# Driver_Board_Invert.net
KiCad netlist of a schematic drawn in EAGLE
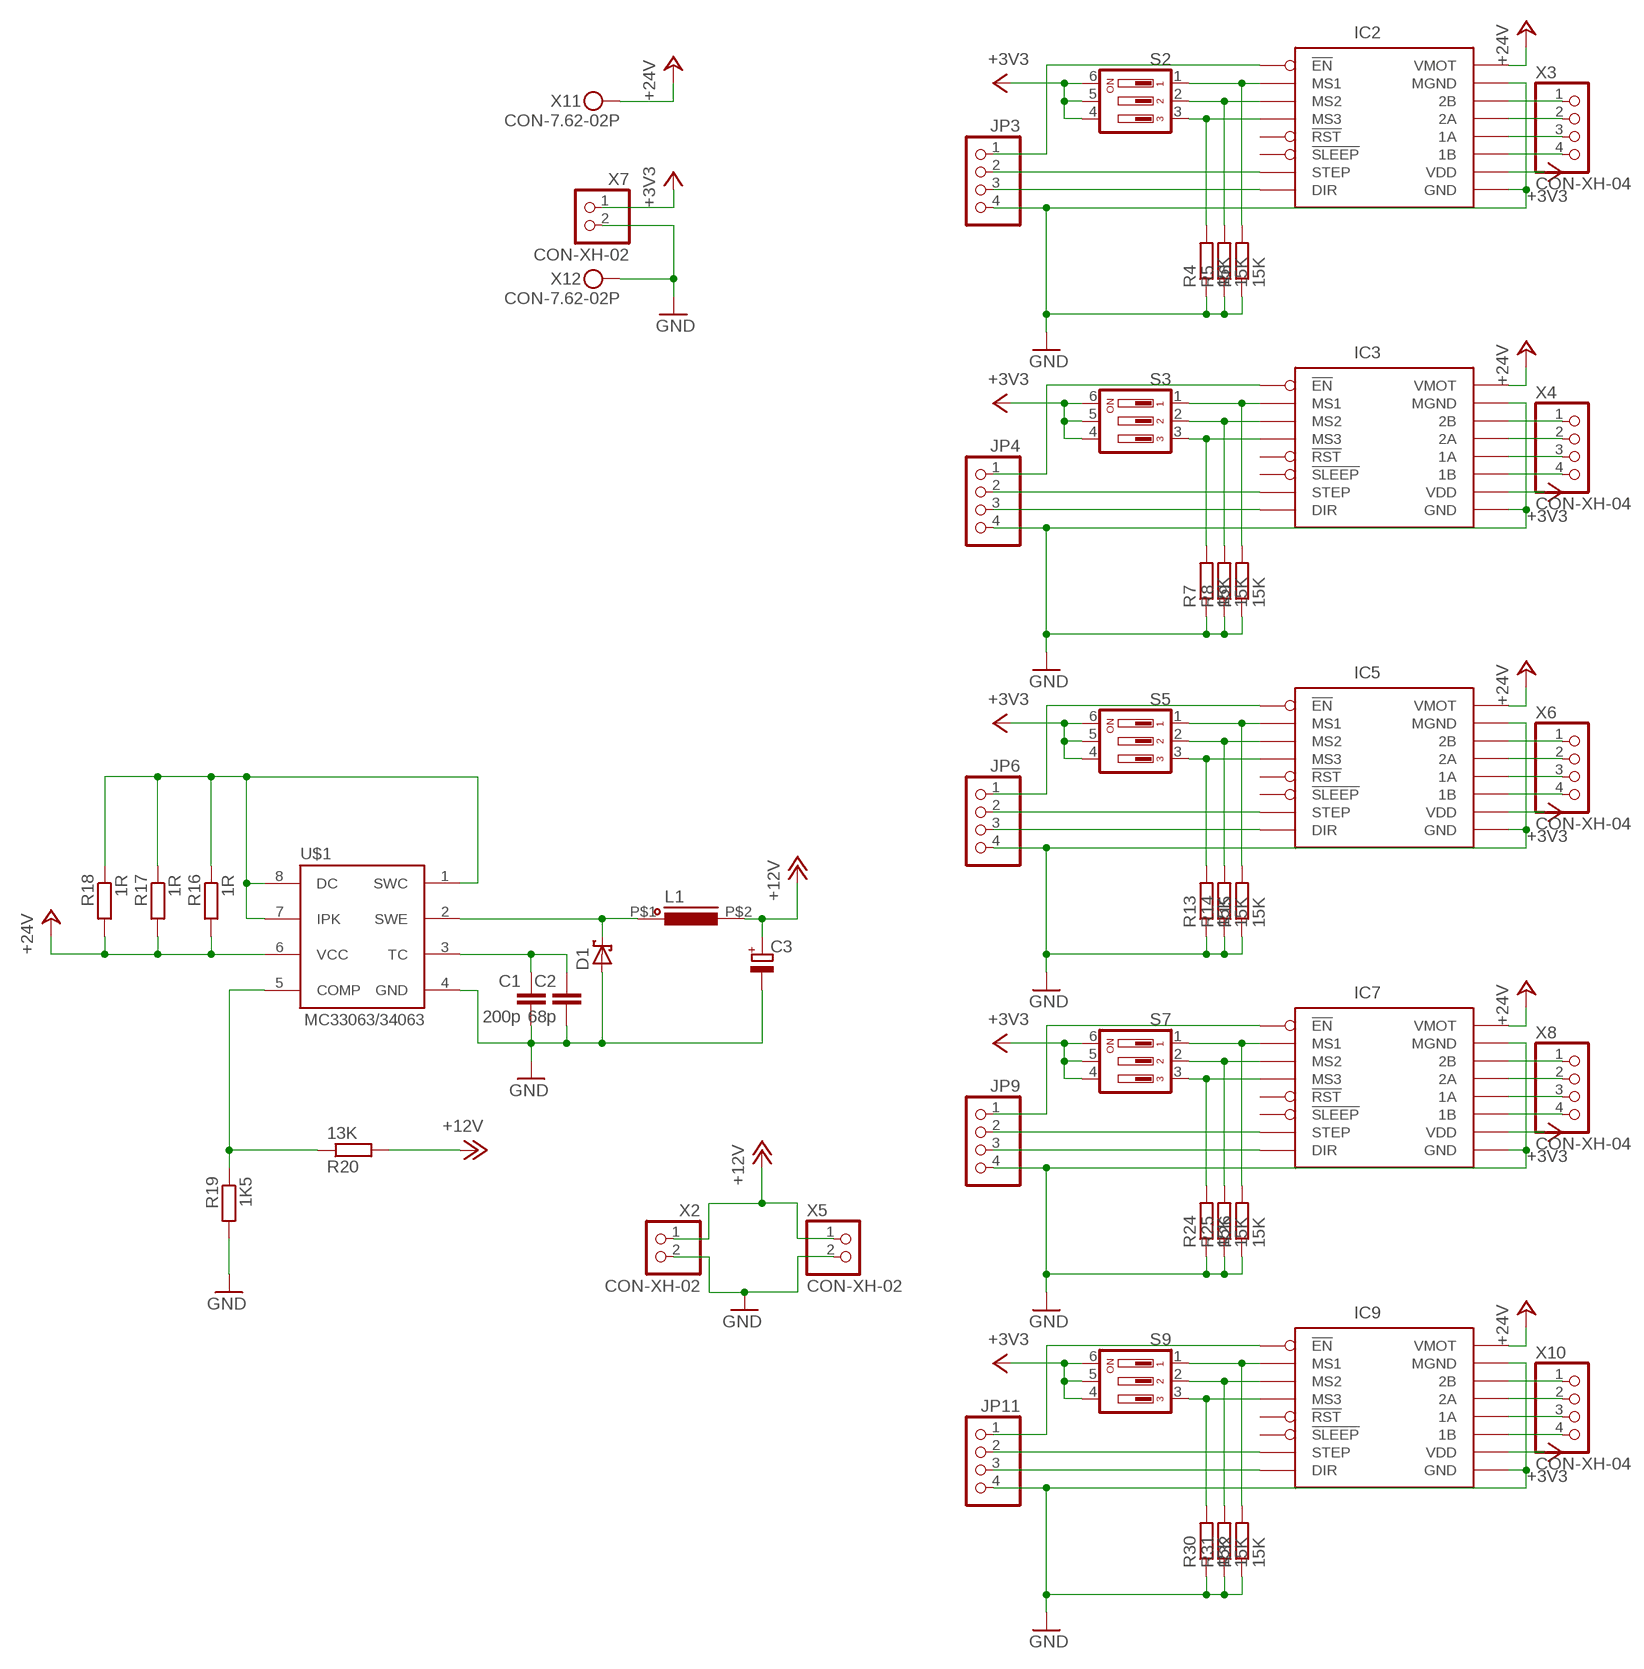
[diagram p0: schematic, sheet 1]

(export (version "E")
  (design (tool "Eeschema 10.0.6"))
  (components
    (comp (ref "C1")
      (value "200p")
      (footprint "eagle-import:C0805")
      (libsource (lib "eagle-import") (part "CAP_0805"))
    )
    (comp (ref "C2")
      (value "68p")
      (footprint "eagle-import:C0805")
      (libsource (lib "eagle-import") (part "CAP_0805"))
    )
    (comp (ref "C3")
      (value "CAP-POL_E3.5-8")
      (footprint "eagle-import:E3,5-8")
      (libsource (lib "eagle-import") (part "CAP-POL_E3.5-8"))
    )
    (comp (ref "D1")
      (value "DIODE-SH_SMA")
      (footprint "eagle-import:DO214AC")
      (libsource (lib "eagle-import") (part "DIODE-SH_SMA"))
    )
    (comp (ref "IC2")
      (value "STEP-DRVST820-REV")
      (footprint "eagle-import:DRV-ST820-REV")
      (libsource (lib "eagle-import") (part "STEP-DRVST820-REV"))
    )
    (comp (ref "IC3")
      (value "STEP-DRVST820-REV")
      (footprint "eagle-import:DRV-ST820-REV")
      (libsource (lib "eagle-import") (part "STEP-DRVST820-REV"))
    )
    (comp (ref "IC5")
      (value "STEP-DRVST820-REV")
      (footprint "eagle-import:DRV-ST820-REV")
      (libsource (lib "eagle-import") (part "STEP-DRVST820-REV"))
    )
    (comp (ref "IC7")
      (value "STEP-DRVST820-REV")
      (footprint "eagle-import:DRV-ST820-REV")
      (libsource (lib "eagle-import") (part "STEP-DRVST820-REV"))
    )
    (comp (ref "IC9")
      (value "STEP-DRVST820-REV")
      (footprint "eagle-import:DRV-ST820-REV")
      (libsource (lib "eagle-import") (part "STEP-DRVST820-REV"))
    )
    (comp (ref "JP3")
      (value "PINHD-1X4")
      (footprint "eagle-import:1X04")
      (libsource (lib "eagle-import") (part "PINHD-1X4"))
    )
    (comp (ref "JP4")
      (value "PINHD-1X4")
      (footprint "eagle-import:1X04")
      (libsource (lib "eagle-import") (part "PINHD-1X4"))
    )
    (comp (ref "JP6")
      (value "PINHD-1X4")
      (footprint "eagle-import:1X04")
      (libsource (lib "eagle-import") (part "PINHD-1X4"))
    )
    (comp (ref "JP9")
      (value "PINHD-1X4")
      (footprint "eagle-import:1X04")
      (libsource (lib "eagle-import") (part "PINHD-1X4"))
    )
    (comp (ref "JP11")
      (value "PINHD-1X4")
      (footprint "eagle-import:1X04")
      (libsource (lib "eagle-import") (part "PINHD-1X4"))
    )
    (comp (ref "L1")
      (value "INDUCTORCW68")
      (footprint "eagle-import:CW68")
      (libsource (lib "eagle-import") (part "INDUCTORCW68"))
    )
    (comp (ref "R4")
      (value "15K")
      (footprint "eagle-import:RESC2012X50")
      (libsource (lib "eagle-import") (part "R_R0805"))
    )
    (comp (ref "R5")
      (value "15K")
      (footprint "eagle-import:RESC2012X50")
      (libsource (lib "eagle-import") (part "R_R0805"))
    )
    (comp (ref "R6")
      (value "15K")
      (footprint "eagle-import:RESC2012X50")
      (libsource (lib "eagle-import") (part "R_R0805"))
    )
    (comp (ref "R7")
      (value "15K")
      (footprint "eagle-import:RESC2012X50")
      (libsource (lib "eagle-import") (part "R_R0805"))
    )
    (comp (ref "R8")
      (value "15K")
      (footprint "eagle-import:RESC2012X50")
      (libsource (lib "eagle-import") (part "R_R0805"))
    )
    (comp (ref "R9")
      (value "15K")
      (footprint "eagle-import:RESC2012X50")
      (libsource (lib "eagle-import") (part "R_R0805"))
    )
    (comp (ref "R13")
      (value "15K")
      (footprint "eagle-import:RESC2012X50")
      (libsource (lib "eagle-import") (part "R_R0805"))
    )
    (comp (ref "R14")
      (value "15K")
      (footprint "eagle-import:RESC2012X50")
      (libsource (lib "eagle-import") (part "R_R0805"))
    )
    (comp (ref "R15")
      (value "15K")
      (footprint "eagle-import:RESC2012X50")
      (libsource (lib "eagle-import") (part "R_R0805"))
    )
    (comp (ref "R16")
      (value "1R")
      (footprint "eagle-import:R0805")
      (libsource (lib "eagle-import") (part "R_0805"))
    )
    (comp (ref "R17")
      (value "1R")
      (footprint "eagle-import:R0805")
      (libsource (lib "eagle-import") (part "R_0805"))
    )
    (comp (ref "R18")
      (value "1R")
      (footprint "eagle-import:R0805")
      (libsource (lib "eagle-import") (part "R_0805"))
    )
    (comp (ref "R19")
      (value "1K5")
      (footprint "eagle-import:R0805")
      (libsource (lib "eagle-import") (part "R_0805"))
    )
    (comp (ref "R20")
      (value "13K")
      (footprint "eagle-import:R0805")
      (libsource (lib "eagle-import") (part "R_0805"))
    )
    (comp (ref "R24")
      (value "15K")
      (footprint "eagle-import:RESC2012X50")
      (libsource (lib "eagle-import") (part "R_R0805"))
    )
    (comp (ref "R25")
      (value "15K")
      (footprint "eagle-import:RESC2012X50")
      (libsource (lib "eagle-import") (part "R_R0805"))
    )
    (comp (ref "R26")
      (value "15K")
      (footprint "eagle-import:RESC2012X50")
      (libsource (lib "eagle-import") (part "R_R0805"))
    )
    (comp (ref "R30")
      (value "15K")
      (footprint "eagle-import:RESC2012X50")
      (libsource (lib "eagle-import") (part "R_R0805"))
    )
    (comp (ref "R31")
      (value "15K")
      (footprint "eagle-import:RESC2012X50")
      (libsource (lib "eagle-import") (part "R_R0805"))
    )
    (comp (ref "R32")
      (value "15K")
      (footprint "eagle-import:RESC2012X50")
      (libsource (lib "eagle-import") (part "R_R0805"))
    )
    (comp (ref "S2")
      (value "SW-DIP03S")
      (footprint "eagle-import:DIP03YL")
      (libsource (lib "eagle-import") (part "SW-DIP03S"))
    )
    (comp (ref "S3")
      (value "SW-DIP03S")
      (footprint "eagle-import:DIP03YL")
      (libsource (lib "eagle-import") (part "SW-DIP03S"))
    )
    (comp (ref "S5")
      (value "SW-DIP03S")
      (footprint "eagle-import:DIP03YL")
      (libsource (lib "eagle-import") (part "SW-DIP03S"))
    )
    (comp (ref "S7")
      (value "SW-DIP03S")
      (footprint "eagle-import:DIP03YL")
      (libsource (lib "eagle-import") (part "SW-DIP03S"))
    )
    (comp (ref "S9")
      (value "SW-DIP03S")
      (footprint "eagle-import:DIP03YL")
      (libsource (lib "eagle-import") (part "SW-DIP03S"))
    )
    (comp (ref "U$1")
      (value "MC33063/MC34063P")
      (footprint "eagle-import:DIL08")
      (libsource (lib "eagle-import") (part "MC33063/MC34063P"))
    )
    (comp (ref "X1")
      (value "CON-7.62-02P")
      (footprint "eagle-import:KF25C-7.62-02P-13")
      (libsource (lib "eagle-import") (part "CON-7.62-02P"))
    )
    (comp (ref "X2")
      (value "CON-XH-02")
      (footprint "eagle-import:XH-02")
      (libsource (lib "eagle-import") (part "CON-XH-02"))
    )
    (comp (ref "X3")
      (value "CON-XH-04")
      (footprint "eagle-import:XH-04")
      (libsource (lib "eagle-import") (part "CON-XH-04"))
    )
    (comp (ref "X4")
      (value "CON-XH-04")
      (footprint "eagle-import:XH-04")
      (libsource (lib "eagle-import") (part "CON-XH-04"))
    )
    (comp (ref "X5")
      (value "CON-XH-02")
      (footprint "eagle-import:XH-02")
      (libsource (lib "eagle-import") (part "CON-XH-02"))
    )
    (comp (ref "X6")
      (value "CON-XH-04")
      (footprint "eagle-import:XH-04")
      (libsource (lib "eagle-import") (part "CON-XH-04"))
    )
    (comp (ref "X7")
      (value "CON-XH-02")
      (footprint "eagle-import:XH-02")
      (libsource (lib "eagle-import") (part "CON-XH-02"))
    )
    (comp (ref "X8")
      (value "CON-XH-04")
      (footprint "eagle-import:XH-04")
      (libsource (lib "eagle-import") (part "CON-XH-04"))
    )
    (comp (ref "X10")
      (value "CON-XH-04")
      (footprint "eagle-import:XH-04")
      (libsource (lib "eagle-import") (part "CON-XH-04"))
    )
  )
  (nets
    (net (code "1") (name "+3V3") (class "Default")
      (node (ref "IC2") (pin "VDD") (pinfunction "VDD_VDD") (pintype "bidirectional"))
      (node (ref "IC3") (pin "VDD") (pinfunction "VDD_VDD") (pintype "bidirectional"))
      (node (ref "IC5") (pin "VDD") (pinfunction "VDD_VDD") (pintype "bidirectional"))
      (node (ref "IC7") (pin "VDD") (pinfunction "VDD_VDD") (pintype "bidirectional"))
      (node (ref "IC9") (pin "VDD") (pinfunction "VDD_VDD") (pintype "bidirectional"))
      (node (ref "S2") (pin "4") (pinfunction "4_4") (pintype "passive"))
      (node (ref "S2") (pin "5") (pinfunction "5_5") (pintype "passive"))
      (node (ref "S2") (pin "6") (pinfunction "6_6") (pintype "passive"))
      (node (ref "S3") (pin "4") (pinfunction "4_4") (pintype "passive"))
      (node (ref "S3") (pin "5") (pinfunction "5_5") (pintype "passive"))
      (node (ref "S3") (pin "6") (pinfunction "6_6") (pintype "passive"))
      (node (ref "S5") (pin "4") (pinfunction "4_4") (pintype "passive"))
      (node (ref "S5") (pin "5") (pinfunction "5_5") (pintype "passive"))
      (node (ref "S5") (pin "6") (pinfunction "6_6") (pintype "passive"))
      (node (ref "S7") (pin "4") (pinfunction "4_4") (pintype "passive"))
      (node (ref "S7") (pin "5") (pinfunction "5_5") (pintype "passive"))
      (node (ref "S7") (pin "6") (pinfunction "6_6") (pintype "passive"))
      (node (ref "S9") (pin "4") (pinfunction "4_4") (pintype "passive"))
      (node (ref "S9") (pin "5") (pinfunction "5_5") (pintype "passive"))
      (node (ref "S9") (pin "6") (pinfunction "6_6") (pintype "passive"))
      (node (ref "X7") (pin "1") (pinfunction "1_1") (pintype "passive"))
    )
    (net (code "2") (name "+12V") (class "Default")
      (node (ref "C3") (pin "+") (pinfunction "+_+") (pintype "passive"))
      (node (ref "L1") (pin "P$2") (pinfunction "2_P$2") (pintype "passive"))
      (node (ref "R20") (pin "2") (pinfunction "2_2") (pintype "passive"))
      (node (ref "X2") (pin "1") (pinfunction "1_1") (pintype "passive"))
      (node (ref "X5") (pin "1") (pinfunction "1_1") (pintype "passive"))
    )
    (net (code "3") (name "+24V") (class "Default")
      (node (ref "IC2") (pin "VM") (pinfunction "VMOT_VM") (pintype "bidirectional"))
      (node (ref "IC3") (pin "VM") (pinfunction "VMOT_VM") (pintype "bidirectional"))
      (node (ref "IC5") (pin "VM") (pinfunction "VMOT_VM") (pintype "bidirectional"))
      (node (ref "IC7") (pin "VM") (pinfunction "VMOT_VM") (pintype "bidirectional"))
      (node (ref "IC9") (pin "VM") (pinfunction "VMOT_VM") (pintype "bidirectional"))
      (node (ref "R16") (pin "2") (pinfunction "2_2") (pintype "passive"))
      (node (ref "R17") (pin "2") (pinfunction "2_2") (pintype "passive"))
      (node (ref "R18") (pin "2") (pinfunction "2_2") (pintype "passive"))
      (node (ref "U$1") (pin "6") (pinfunction "VCC_6") (pintype "power_in"))
      (node (ref "X1") (pin "P$1") (pinfunction "KL_P$1") (pintype "passive"))
    )
    (net (code "4") (name "GND") (class "Default")
      (node (ref "C1") (pin "2") (pinfunction "2_2") (pintype "passive"))
      (node (ref "C2") (pin "2") (pinfunction "2_2") (pintype "passive"))
      (node (ref "C3") (pin "-") (pinfunction "-_-") (pintype "passive"))
      (node (ref "D1") (pin "A") (pinfunction "A_A") (pintype "passive"))
      (node (ref "IC2") (pin "GND@1") (pinfunction "MGND_GND@1") (pintype "bidirectional"))
      (node (ref "IC2") (pin "GND@2") (pinfunction "GND_GND@2") (pintype "bidirectional"))
      (node (ref "IC3") (pin "GND@1") (pinfunction "MGND_GND@1") (pintype "bidirectional"))
      (node (ref "IC3") (pin "GND@2") (pinfunction "GND_GND@2") (pintype "bidirectional"))
      (node (ref "IC5") (pin "GND@1") (pinfunction "MGND_GND@1") (pintype "bidirectional"))
      (node (ref "IC5") (pin "GND@2") (pinfunction "GND_GND@2") (pintype "bidirectional"))
      (node (ref "IC7") (pin "GND@1") (pinfunction "MGND_GND@1") (pintype "bidirectional"))
      (node (ref "IC7") (pin "GND@2") (pinfunction "GND_GND@2") (pintype "bidirectional"))
      (node (ref "IC9") (pin "GND@1") (pinfunction "MGND_GND@1") (pintype "bidirectional"))
      (node (ref "IC9") (pin "GND@2") (pinfunction "GND_GND@2") (pintype "bidirectional"))
      (node (ref "JP11") (pin "4") (pinfunction "4_4") (pintype "passive"))
      (node (ref "JP3") (pin "4") (pinfunction "4_4") (pintype "passive"))
      (node (ref "JP4") (pin "4") (pinfunction "4_4") (pintype "passive"))
      (node (ref "JP6") (pin "4") (pinfunction "4_4") (pintype "passive"))
      (node (ref "JP9") (pin "4") (pinfunction "4_4") (pintype "passive"))
      (node (ref "R13") (pin "1") (pinfunction "1_1") (pintype "passive"))
      (node (ref "R14") (pin "1") (pinfunction "1_1") (pintype "passive"))
      (node (ref "R15") (pin "1") (pinfunction "1_1") (pintype "passive"))
      (node (ref "R19") (pin "2") (pinfunction "2_2") (pintype "passive"))
      (node (ref "R24") (pin "1") (pinfunction "1_1") (pintype "passive"))
      (node (ref "R25") (pin "1") (pinfunction "1_1") (pintype "passive"))
      (node (ref "R26") (pin "1") (pinfunction "1_1") (pintype "passive"))
      (node (ref "R30") (pin "1") (pinfunction "1_1") (pintype "passive"))
      (node (ref "R31") (pin "1") (pinfunction "1_1") (pintype "passive"))
      (node (ref "R32") (pin "1") (pinfunction "1_1") (pintype "passive"))
      (node (ref "R4") (pin "1") (pinfunction "1_1") (pintype "passive"))
      (node (ref "R5") (pin "1") (pinfunction "1_1") (pintype "passive"))
      (node (ref "R6") (pin "1") (pinfunction "1_1") (pintype "passive"))
      (node (ref "R7") (pin "1") (pinfunction "1_1") (pintype "passive"))
      (node (ref "R8") (pin "1") (pinfunction "1_1") (pintype "passive"))
      (node (ref "R9") (pin "1") (pinfunction "1_1") (pintype "passive"))
      (node (ref "U$1") (pin "4") (pinfunction "GND_4") (pintype "power_in"))
      (node (ref "X1") (pin "P$2") (pinfunction "KL_P$2") (pintype "passive"))
      (node (ref "X2") (pin "2") (pinfunction "2_2") (pintype "passive"))
      (node (ref "X5") (pin "2") (pinfunction "2_2") (pintype "passive"))
      (node (ref "X7") (pin "2") (pinfunction "2_2") (pintype "passive"))
    )
    (net (code "5") (name "Net-(IC2-1A)") (class "Default")
      (node (ref "IC2") (pin "2A") (pinfunction "1A_2A") (pintype "bidirectional"))
      (node (ref "X3") (pin "3") (pinfunction "3_3") (pintype "passive"))
    )
    (net (code "6") (name "Net-(IC2-1B)") (class "Default")
      (node (ref "IC2") (pin "1A") (pinfunction "1B_1A") (pintype "bidirectional"))
      (node (ref "X3") (pin "4") (pinfunction "4_4") (pintype "passive"))
    )
    (net (code "7") (name "Net-(IC2-2A)") (class "Default")
      (node (ref "IC2") (pin "2B") (pinfunction "2A_2B") (pintype "bidirectional"))
      (node (ref "X3") (pin "2") (pinfunction "2_2") (pintype "passive"))
    )
    (net (code "8") (name "Net-(IC2-2B)") (class "Default")
      (node (ref "IC2") (pin "1B") (pinfunction "2B_1B") (pintype "bidirectional"))
      (node (ref "X3") (pin "1") (pinfunction "1_1") (pintype "passive"))
    )
    (net (code "9") (name "Net-(IC2-MS1)") (class "Default")
      (node (ref "IC2") (pin "MS0") (pinfunction "MS1_MS0") (pintype "bidirectional"))
      (node (ref "R6") (pin "2") (pinfunction "2_2") (pintype "passive"))
      (node (ref "S2") (pin "1") (pinfunction "1_1") (pintype "passive"))
    )
    (net (code "10") (name "Net-(IC2-MS2)") (class "Default")
      (node (ref "IC2") (pin "MS1") (pinfunction "MS2_MS1") (pintype "bidirectional"))
      (node (ref "R5") (pin "2") (pinfunction "2_2") (pintype "passive"))
      (node (ref "S2") (pin "2") (pinfunction "2_2") (pintype "passive"))
    )
    (net (code "11") (name "Net-(IC2-MS3)") (class "Default")
      (node (ref "IC2") (pin "MS2") (pinfunction "MS3_MS2") (pintype "bidirectional"))
      (node (ref "R4") (pin "2") (pinfunction "2_2") (pintype "passive"))
      (node (ref "S2") (pin "3") (pinfunction "3_3") (pintype "passive"))
    )
    (net (code "12") (name "Net-(IC2-PadDIR)") (class "Default")
      (node (ref "IC2") (pin "DIR") (pinfunction "DIR_DIR") (pintype "bidirectional"))
      (node (ref "JP3") (pin "3") (pinfunction "3_3") (pintype "passive"))
    )
    (net (code "13") (name "Net-(IC2-PadSTEP)") (class "Default")
      (node (ref "IC2") (pin "STEP") (pinfunction "STEP_STEP") (pintype "bidirectional"))
      (node (ref "JP3") (pin "2") (pinfunction "2_2") (pintype "passive"))
    )
    (net (code "14") (name "Net-(IC2-~{EN})") (class "Default")
      (node (ref "IC2") (pin "EN") (pinfunction "~{EN}_EN") (pintype "bidirectional"))
      (node (ref "JP3") (pin "1") (pinfunction "1_1") (pintype "passive"))
    )
    (net (code "15") (name "Net-(IC3-1A)") (class "Default")
      (node (ref "IC3") (pin "2A") (pinfunction "1A_2A") (pintype "bidirectional"))
      (node (ref "X4") (pin "3") (pinfunction "3_3") (pintype "passive"))
    )
    (net (code "16") (name "Net-(IC3-1B)") (class "Default")
      (node (ref "IC3") (pin "1A") (pinfunction "1B_1A") (pintype "bidirectional"))
      (node (ref "X4") (pin "4") (pinfunction "4_4") (pintype "passive"))
    )
    (net (code "17") (name "Net-(IC3-2A)") (class "Default")
      (node (ref "IC3") (pin "2B") (pinfunction "2A_2B") (pintype "bidirectional"))
      (node (ref "X4") (pin "2") (pinfunction "2_2") (pintype "passive"))
    )
    (net (code "18") (name "Net-(IC3-2B)") (class "Default")
      (node (ref "IC3") (pin "1B") (pinfunction "2B_1B") (pintype "bidirectional"))
      (node (ref "X4") (pin "1") (pinfunction "1_1") (pintype "passive"))
    )
    (net (code "19") (name "Net-(IC3-MS1)") (class "Default")
      (node (ref "IC3") (pin "MS0") (pinfunction "MS1_MS0") (pintype "bidirectional"))
      (node (ref "R9") (pin "2") (pinfunction "2_2") (pintype "passive"))
      (node (ref "S3") (pin "1") (pinfunction "1_1") (pintype "passive"))
    )
    (net (code "20") (name "Net-(IC3-MS2)") (class "Default")
      (node (ref "IC3") (pin "MS1") (pinfunction "MS2_MS1") (pintype "bidirectional"))
      (node (ref "R8") (pin "2") (pinfunction "2_2") (pintype "passive"))
      (node (ref "S3") (pin "2") (pinfunction "2_2") (pintype "passive"))
    )
    (net (code "21") (name "Net-(IC3-MS3)") (class "Default")
      (node (ref "IC3") (pin "MS2") (pinfunction "MS3_MS2") (pintype "bidirectional"))
      (node (ref "R7") (pin "2") (pinfunction "2_2") (pintype "passive"))
      (node (ref "S3") (pin "3") (pinfunction "3_3") (pintype "passive"))
    )
    (net (code "22") (name "Net-(IC3-PadDIR)") (class "Default")
      (node (ref "IC3") (pin "DIR") (pinfunction "DIR_DIR") (pintype "bidirectional"))
      (node (ref "JP4") (pin "3") (pinfunction "3_3") (pintype "passive"))
    )
    (net (code "23") (name "Net-(IC3-PadSTEP)") (class "Default")
      (node (ref "IC3") (pin "STEP") (pinfunction "STEP_STEP") (pintype "bidirectional"))
      (node (ref "JP4") (pin "2") (pinfunction "2_2") (pintype "passive"))
    )
    (net (code "24") (name "Net-(IC3-~{EN})") (class "Default")
      (node (ref "IC3") (pin "EN") (pinfunction "~{EN}_EN") (pintype "bidirectional"))
      (node (ref "JP4") (pin "1") (pinfunction "1_1") (pintype "passive"))
    )
    (net (code "25") (name "Net-(IC5-1A)") (class "Default")
      (node (ref "IC5") (pin "2A") (pinfunction "1A_2A") (pintype "bidirectional"))
      (node (ref "X6") (pin "3") (pinfunction "3_3") (pintype "passive"))
    )
    (net (code "26") (name "Net-(IC5-1B)") (class "Default")
      (node (ref "IC5") (pin "1A") (pinfunction "1B_1A") (pintype "bidirectional"))
      (node (ref "X6") (pin "4") (pinfunction "4_4") (pintype "passive"))
    )
    (net (code "27") (name "Net-(IC5-2A)") (class "Default")
      (node (ref "IC5") (pin "2B") (pinfunction "2A_2B") (pintype "bidirectional"))
      (node (ref "X6") (pin "2") (pinfunction "2_2") (pintype "passive"))
    )
    (net (code "28") (name "Net-(IC5-2B)") (class "Default")
      (node (ref "IC5") (pin "1B") (pinfunction "2B_1B") (pintype "bidirectional"))
      (node (ref "X6") (pin "1") (pinfunction "1_1") (pintype "passive"))
    )
    (net (code "29") (name "Net-(IC5-MS1)") (class "Default")
      (node (ref "IC5") (pin "MS0") (pinfunction "MS1_MS0") (pintype "bidirectional"))
      (node (ref "R15") (pin "2") (pinfunction "2_2") (pintype "passive"))
      (node (ref "S5") (pin "1") (pinfunction "1_1") (pintype "passive"))
    )
    (net (code "30") (name "Net-(IC5-MS2)") (class "Default")
      (node (ref "IC5") (pin "MS1") (pinfunction "MS2_MS1") (pintype "bidirectional"))
      (node (ref "R14") (pin "2") (pinfunction "2_2") (pintype "passive"))
      (node (ref "S5") (pin "2") (pinfunction "2_2") (pintype "passive"))
    )
    (net (code "31") (name "Net-(IC5-MS3)") (class "Default")
      (node (ref "IC5") (pin "MS2") (pinfunction "MS3_MS2") (pintype "bidirectional"))
      (node (ref "R13") (pin "2") (pinfunction "2_2") (pintype "passive"))
      (node (ref "S5") (pin "3") (pinfunction "3_3") (pintype "passive"))
    )
    (net (code "32") (name "Net-(IC5-PadDIR)") (class "Default")
      (node (ref "IC5") (pin "DIR") (pinfunction "DIR_DIR") (pintype "bidirectional"))
      (node (ref "JP6") (pin "3") (pinfunction "3_3") (pintype "passive"))
    )
    (net (code "33") (name "Net-(IC5-PadSTEP)") (class "Default")
      (node (ref "IC5") (pin "STEP") (pinfunction "STEP_STEP") (pintype "bidirectional"))
      (node (ref "JP6") (pin "2") (pinfunction "2_2") (pintype "passive"))
    )
    (net (code "34") (name "Net-(IC5-~{EN})") (class "Default")
      (node (ref "IC5") (pin "EN") (pinfunction "~{EN}_EN") (pintype "bidirectional"))
      (node (ref "JP6") (pin "1") (pinfunction "1_1") (pintype "passive"))
    )
    (net (code "35") (name "Net-(IC7-1A)") (class "Default")
      (node (ref "IC7") (pin "2A") (pinfunction "1A_2A") (pintype "bidirectional"))
      (node (ref "X8") (pin "3") (pinfunction "3_3") (pintype "passive"))
    )
    (net (code "36") (name "Net-(IC7-1B)") (class "Default")
      (node (ref "IC7") (pin "1A") (pinfunction "1B_1A") (pintype "bidirectional"))
      (node (ref "X8") (pin "4") (pinfunction "4_4") (pintype "passive"))
    )
    (net (code "37") (name "Net-(IC7-2A)") (class "Default")
      (node (ref "IC7") (pin "2B") (pinfunction "2A_2B") (pintype "bidirectional"))
      (node (ref "X8") (pin "2") (pinfunction "2_2") (pintype "passive"))
    )
    (net (code "38") (name "Net-(IC7-2B)") (class "Default")
      (node (ref "IC7") (pin "1B") (pinfunction "2B_1B") (pintype "bidirectional"))
      (node (ref "X8") (pin "1") (pinfunction "1_1") (pintype "passive"))
    )
    (net (code "39") (name "Net-(IC7-MS1)") (class "Default")
      (node (ref "IC7") (pin "MS0") (pinfunction "MS1_MS0") (pintype "bidirectional"))
      (node (ref "R26") (pin "2") (pinfunction "2_2") (pintype "passive"))
      (node (ref "S7") (pin "1") (pinfunction "1_1") (pintype "passive"))
    )
    (net (code "40") (name "Net-(IC7-MS2)") (class "Default")
      (node (ref "IC7") (pin "MS1") (pinfunction "MS2_MS1") (pintype "bidirectional"))
      (node (ref "R25") (pin "2") (pinfunction "2_2") (pintype "passive"))
      (node (ref "S7") (pin "2") (pinfunction "2_2") (pintype "passive"))
    )
    (net (code "41") (name "Net-(IC7-MS3)") (class "Default")
      (node (ref "IC7") (pin "MS2") (pinfunction "MS3_MS2") (pintype "bidirectional"))
      (node (ref "R24") (pin "2") (pinfunction "2_2") (pintype "passive"))
      (node (ref "S7") (pin "3") (pinfunction "3_3") (pintype "passive"))
    )
    (net (code "42") (name "Net-(IC7-PadDIR)") (class "Default")
      (node (ref "IC7") (pin "DIR") (pinfunction "DIR_DIR") (pintype "bidirectional"))
      (node (ref "JP9") (pin "3") (pinfunction "3_3") (pintype "passive"))
    )
    (net (code "43") (name "Net-(IC7-PadSTEP)") (class "Default")
      (node (ref "IC7") (pin "STEP") (pinfunction "STEP_STEP") (pintype "bidirectional"))
      (node (ref "JP9") (pin "2") (pinfunction "2_2") (pintype "passive"))
    )
    (net (code "44") (name "Net-(IC7-~{EN})") (class "Default")
      (node (ref "IC7") (pin "EN") (pinfunction "~{EN}_EN") (pintype "bidirectional"))
      (node (ref "JP9") (pin "1") (pinfunction "1_1") (pintype "passive"))
    )
    (net (code "45") (name "Net-(IC9-1A)") (class "Default")
      (node (ref "IC9") (pin "2A") (pinfunction "1A_2A") (pintype "bidirectional"))
      (node (ref "X10") (pin "3") (pinfunction "3_3") (pintype "passive"))
    )
    (net (code "46") (name "Net-(IC9-1B)") (class "Default")
      (node (ref "IC9") (pin "1A") (pinfunction "1B_1A") (pintype "bidirectional"))
      (node (ref "X10") (pin "4") (pinfunction "4_4") (pintype "passive"))
    )
    (net (code "47") (name "Net-(IC9-2A)") (class "Default")
      (node (ref "IC9") (pin "2B") (pinfunction "2A_2B") (pintype "bidirectional"))
      (node (ref "X10") (pin "2") (pinfunction "2_2") (pintype "passive"))
    )
    (net (code "48") (name "Net-(IC9-2B)") (class "Default")
      (node (ref "IC9") (pin "1B") (pinfunction "2B_1B") (pintype "bidirectional"))
      (node (ref "X10") (pin "1") (pinfunction "1_1") (pintype "passive"))
    )
    (net (code "49") (name "Net-(IC9-MS1)") (class "Default")
      (node (ref "IC9") (pin "MS0") (pinfunction "MS1_MS0") (pintype "bidirectional"))
      (node (ref "R32") (pin "2") (pinfunction "2_2") (pintype "passive"))
      (node (ref "S9") (pin "1") (pinfunction "1_1") (pintype "passive"))
    )
    (net (code "50") (name "Net-(IC9-MS2)") (class "Default")
      (node (ref "IC9") (pin "MS1") (pinfunction "MS2_MS1") (pintype "bidirectional"))
      (node (ref "R31") (pin "2") (pinfunction "2_2") (pintype "passive"))
      (node (ref "S9") (pin "2") (pinfunction "2_2") (pintype "passive"))
    )
    (net (code "51") (name "Net-(IC9-MS3)") (class "Default")
      (node (ref "IC9") (pin "MS2") (pinfunction "MS3_MS2") (pintype "bidirectional"))
      (node (ref "R30") (pin "2") (pinfunction "2_2") (pintype "passive"))
      (node (ref "S9") (pin "3") (pinfunction "3_3") (pintype "passive"))
    )
    (net (code "52") (name "Net-(IC9-PadDIR)") (class "Default")
      (node (ref "IC9") (pin "DIR") (pinfunction "DIR_DIR") (pintype "bidirectional"))
      (node (ref "JP11") (pin "3") (pinfunction "3_3") (pintype "passive"))
    )
    (net (code "53") (name "Net-(IC9-PadSTEP)") (class "Default")
      (node (ref "IC9") (pin "STEP") (pinfunction "STEP_STEP") (pintype "bidirectional"))
      (node (ref "JP11") (pin "2") (pinfunction "2_2") (pintype "passive"))
    )
    (net (code "54") (name "Net-(IC9-~{EN})") (class "Default")
      (node (ref "IC9") (pin "EN") (pinfunction "~{EN}_EN") (pintype "bidirectional"))
      (node (ref "JP11") (pin "1") (pinfunction "1_1") (pintype "passive"))
    )
    (net (code "55") (name "Net-(L1-1)") (class "Default")
      (node (ref "D1") (pin "C") (pinfunction "C_C") (pintype "passive"))
      (node (ref "L1") (pin "P$1") (pinfunction "1_P$1") (pintype "passive"))
      (node (ref "U$1") (pin "2") (pinfunction "SWE_2") (pintype "input"))
    )
    (net (code "56") (name "Net-(U$1-COMP)") (class "Default")
      (node (ref "R19") (pin "1") (pinfunction "1_1") (pintype "passive"))
      (node (ref "R20") (pin "1") (pinfunction "1_1") (pintype "passive"))
      (node (ref "U$1") (pin "5") (pinfunction "COMP_5") (pintype "input"))
    )
    (net (code "57") (name "Net-(U$1-DC)") (class "Default")
      (node (ref "R16") (pin "1") (pinfunction "1_1") (pintype "passive"))
      (node (ref "R17") (pin "1") (pinfunction "1_1") (pintype "passive"))
      (node (ref "R18") (pin "1") (pinfunction "1_1") (pintype "passive"))
      (node (ref "U$1") (pin "1") (pinfunction "SWC_1") (pintype "input"))
      (node (ref "U$1") (pin "7") (pinfunction "IPK_7") (pintype "bidirectional"))
      (node (ref "U$1") (pin "8") (pinfunction "DC_8") (pintype "input"))
    )
    (net (code "58") (name "Net-(U$1-TC)") (class "Default")
      (node (ref "C1") (pin "1") (pinfunction "1_1") (pintype "passive"))
      (node (ref "C2") (pin "1") (pinfunction "1_1") (pintype "passive"))
      (node (ref "U$1") (pin "3") (pinfunction "TC_3") (pintype "input"))
    )
    (net (code "59") (name "unconnected-(IC2-~{RST}-PadRST)") (class "Default")
      (node (ref "IC2") (pin "RST") (pinfunction "~{RST}_RST") (pintype "bidirectional"))
    )
    (net (code "60") (name "unconnected-(IC2-~{SLEEP}-PadNC)") (class "Default")
      (node (ref "IC2") (pin "NC") (pinfunction "~{SLEEP}_NC") (pintype "bidirectional"))
    )
    (net (code "61") (name "unconnected-(IC3-~{RST}-PadRST)") (class "Default")
      (node (ref "IC3") (pin "RST") (pinfunction "~{RST}_RST") (pintype "bidirectional"))
    )
    (net (code "62") (name "unconnected-(IC3-~{SLEEP}-PadNC)") (class "Default")
      (node (ref "IC3") (pin "NC") (pinfunction "~{SLEEP}_NC") (pintype "bidirectional"))
    )
    (net (code "63") (name "unconnected-(IC5-~{RST}-PadRST)") (class "Default")
      (node (ref "IC5") (pin "RST") (pinfunction "~{RST}_RST") (pintype "bidirectional"))
    )
    (net (code "64") (name "unconnected-(IC5-~{SLEEP}-PadNC)") (class "Default")
      (node (ref "IC5") (pin "NC") (pinfunction "~{SLEEP}_NC") (pintype "bidirectional"))
    )
    (net (code "65") (name "unconnected-(IC7-~{RST}-PadRST)") (class "Default")
      (node (ref "IC7") (pin "RST") (pinfunction "~{RST}_RST") (pintype "bidirectional"))
    )
    (net (code "66") (name "unconnected-(IC7-~{SLEEP}-PadNC)") (class "Default")
      (node (ref "IC7") (pin "NC") (pinfunction "~{SLEEP}_NC") (pintype "bidirectional"))
    )
    (net (code "67") (name "unconnected-(IC9-~{RST}-PadRST)") (class "Default")
      (node (ref "IC9") (pin "RST") (pinfunction "~{RST}_RST") (pintype "bidirectional"))
    )
    (net (code "68") (name "unconnected-(IC9-~{SLEEP}-PadNC)") (class "Default")
      (node (ref "IC9") (pin "NC") (pinfunction "~{SLEEP}_NC") (pintype "bidirectional"))
    )
  )
)
